# DiamondOutreach.net
KiCad netlist of a schematic drawn in EAGLE
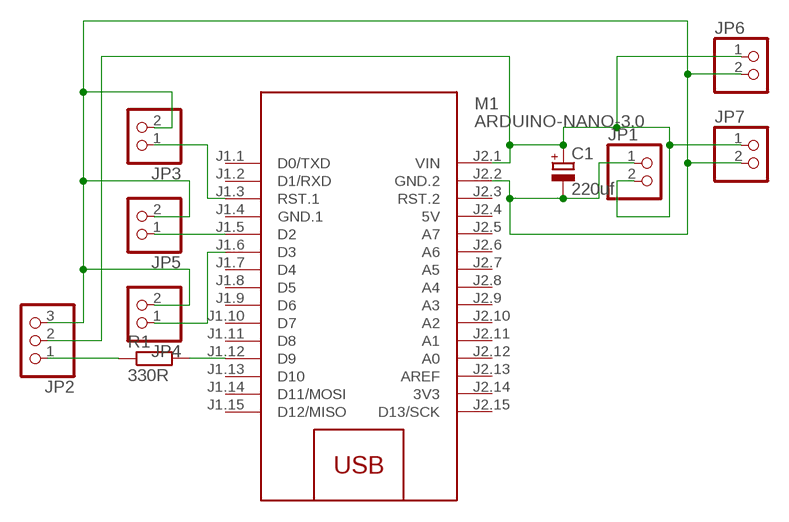
[diagram p0: schematic, sheet 1]

(export (version "E")
  (design (tool "Eeschema 10.0.6"))
  (components
    (comp (ref "C1")
      (value "220uf")
      (footprint "eagle-import:E2,5-6E")
      (libsource (lib "eagle-import") (part "CPOL-EUE2,5-6E"))
    )
    (comp (ref "JP1")
      (value "PINHD-1X2")
      (footprint "eagle-import:1X02")
      (libsource (lib "eagle-import") (part "PINHD-1X2"))
    )
    (comp (ref "JP2")
      (value "PINHD-1X3")
      (footprint "eagle-import:1X03")
      (libsource (lib "eagle-import") (part "PINHD-1X3"))
    )
    (comp (ref "JP3")
      (value "PINHD-1X2")
      (footprint "eagle-import:1X02")
      (libsource (lib "eagle-import") (part "PINHD-1X2"))
    )
    (comp (ref "JP4")
      (value "PINHD-1X2")
      (footprint "eagle-import:1X02")
      (libsource (lib "eagle-import") (part "PINHD-1X2"))
    )
    (comp (ref "JP5")
      (value "PINHD-1X2")
      (footprint "eagle-import:1X02")
      (libsource (lib "eagle-import") (part "PINHD-1X2"))
    )
    (comp (ref "JP6")
      (value "PINHD-1X2")
      (footprint "eagle-import:1X02")
      (libsource (lib "eagle-import") (part "PINHD-1X2"))
    )
    (comp (ref "JP7")
      (value "PINHD-1X2")
      (footprint "eagle-import:1X02")
      (libsource (lib "eagle-import") (part "PINHD-1X2"))
    )
    (comp (ref "M1")
      (value "ARDUINO-NANO-3.0")
      (footprint "eagle-import:ARDUINO-NANO-3.0")
      (libsource (lib "eagle-import") (part "ARDUINO-NANO-3.0"))
    )
    (comp (ref "R1")
      (value "330R")
      (footprint "eagle-import:0204_7")
      (libsource (lib "eagle-import") (part "R-EU_0204/7"))
    )
  )
  (nets
    (net (code "1") (name "/3V3") (class "Default")
      (node (ref "M1") (pin "J2.14") (pinfunction "3V3_J2.14") (pintype "power_in"))
    )
    (net (code "2") (name "/5V") (class "Default")
      (node (ref "M1") (pin "J2.4") (pinfunction "5V_J2.4") (pintype "power_in"))
    )
    (net (code "3") (name "/GND.1") (class "Default")
      (node (ref "M1") (pin "J1.4") (pinfunction "GND.1_J1.4") (pintype "power_in"))
    )
    (net (code "4") (name "Net-(JP2-Pad1)") (class "Default")
      (node (ref "JP2") (pin "1") (pinfunction "1_1") (pintype "passive"))
      (node (ref "R1") (pin "1") (pinfunction "1_1") (pintype "passive"))
    )
    (net (code "5") (name "Net-(M1-D2)") (class "Default")
      (node (ref "JP5") (pin "1") (pinfunction "1_1") (pintype "passive"))
      (node (ref "M1") (pin "J1.5") (pinfunction "D2_J1.5") (pintype "bidirectional"))
    )
    (net (code "6") (name "Net-(M1-D3)") (class "Default")
      (node (ref "JP4") (pin "1") (pinfunction "1_1") (pintype "passive"))
      (node (ref "M1") (pin "J1.6") (pinfunction "D3_J1.6") (pintype "bidirectional"))
    )
    (net (code "7") (name "Net-(M1-D9)") (class "Default")
      (node (ref "M1") (pin "J1.12") (pinfunction "D9_J1.12") (pintype "bidirectional"))
      (node (ref "R1") (pin "2") (pinfunction "2_2") (pintype "passive"))
    )
    (net (code "8") (name "Net-(M1-GND.2)") (class "Default")
      (node (ref "C1") (pin "-") (pinfunction "-_-") (pintype "passive"))
      (node (ref "JP1") (pin "1") (pinfunction "1_1") (pintype "passive"))
      (node (ref "JP2") (pin "3") (pinfunction "3_3") (pintype "passive"))
      (node (ref "JP3") (pin "2") (pinfunction "2_2") (pintype "passive"))
      (node (ref "JP4") (pin "2") (pinfunction "2_2") (pintype "passive"))
      (node (ref "JP5") (pin "2") (pinfunction "2_2") (pintype "passive"))
      (node (ref "JP6") (pin "2") (pinfunction "2_2") (pintype "passive"))
      (node (ref "JP7") (pin "2") (pinfunction "2_2") (pintype "passive"))
      (node (ref "M1") (pin "J2.2") (pinfunction "GND.2_J2.2") (pintype "power_in"))
    )
    (net (code "9") (name "Net-(M1-RST.1)") (class "Default")
      (node (ref "JP3") (pin "1") (pinfunction "1_1") (pintype "passive"))
      (node (ref "M1") (pin "J1.3") (pinfunction "RST.1_J1.3") (pintype "bidirectional"))
    )
    (net (code "10") (name "Net-(M1-VIN)") (class "Default")
      (node (ref "C1") (pin "+") (pinfunction "+_+") (pintype "passive"))
      (node (ref "JP1") (pin "2") (pinfunction "2_2") (pintype "passive"))
      (node (ref "JP2") (pin "2") (pinfunction "2_2") (pintype "passive"))
      (node (ref "JP6") (pin "1") (pinfunction "1_1") (pintype "passive"))
      (node (ref "JP7") (pin "1") (pinfunction "1_1") (pintype "passive"))
      (node (ref "M1") (pin "J2.1") (pinfunction "VIN_J2.1") (pintype "power_in"))
    )
    (net (code "11") (name "unconnected-(M1-A0-PadJ2.12)") (class "Default")
      (node (ref "M1") (pin "J2.12") (pinfunction "A0_J2.12") (pintype "bidirectional"))
    )
    (net (code "12") (name "unconnected-(M1-A1-PadJ2.11)") (class "Default")
      (node (ref "M1") (pin "J2.11") (pinfunction "A1_J2.11") (pintype "bidirectional"))
    )
    (net (code "13") (name "unconnected-(M1-A2-PadJ2.10)") (class "Default")
      (node (ref "M1") (pin "J2.10") (pinfunction "A2_J2.10") (pintype "bidirectional"))
    )
    (net (code "14") (name "unconnected-(M1-A3-PadJ2.9)") (class "Default")
      (node (ref "M1") (pin "J2.9") (pinfunction "A3_J2.9") (pintype "bidirectional"))
    )
    (net (code "15") (name "unconnected-(M1-A4-PadJ2.8)") (class "Default")
      (node (ref "M1") (pin "J2.8") (pinfunction "A4_J2.8") (pintype "bidirectional"))
    )
    (net (code "16") (name "unconnected-(M1-A5-PadJ2.7)") (class "Default")
      (node (ref "M1") (pin "J2.7") (pinfunction "A5_J2.7") (pintype "bidirectional"))
    )
    (net (code "17") (name "unconnected-(M1-A6-PadJ2.6)") (class "Default")
      (node (ref "M1") (pin "J2.6") (pinfunction "A6_J2.6") (pintype "bidirectional"))
    )
    (net (code "18") (name "unconnected-(M1-A7-PadJ2.5)") (class "Default")
      (node (ref "M1") (pin "J2.5") (pinfunction "A7_J2.5") (pintype "bidirectional"))
    )
    (net (code "19") (name "unconnected-(M1-AREF-PadJ2.13)") (class "Default")
      (node (ref "M1") (pin "J2.13") (pinfunction "AREF_J2.13") (pintype "bidirectional"))
    )
    (net (code "20") (name "unconnected-(M1-D0{slash}TXD-PadJ1.1)") (class "Default")
      (node (ref "M1") (pin "J1.1") (pinfunction "D0/TXD_J1.1") (pintype "bidirectional"))
    )
    (net (code "21") (name "unconnected-(M1-D1{slash}RXD-PadJ1.2)") (class "Default")
      (node (ref "M1") (pin "J1.2") (pinfunction "D1/RXD_J1.2") (pintype "bidirectional"))
    )
    (net (code "22") (name "unconnected-(M1-D4-PadJ1.7)") (class "Default")
      (node (ref "M1") (pin "J1.7") (pinfunction "D4_J1.7") (pintype "bidirectional"))
    )
    (net (code "23") (name "unconnected-(M1-D5-PadJ1.8)") (class "Default")
      (node (ref "M1") (pin "J1.8") (pinfunction "D5_J1.8") (pintype "bidirectional"))
    )
    (net (code "24") (name "unconnected-(M1-D6-PadJ1.9)") (class "Default")
      (node (ref "M1") (pin "J1.9") (pinfunction "D6_J1.9") (pintype "bidirectional"))
    )
    (net (code "25") (name "unconnected-(M1-D7-PadJ1.10)") (class "Default")
      (node (ref "M1") (pin "J1.10") (pinfunction "D7_J1.10") (pintype "bidirectional"))
    )
    (net (code "26") (name "unconnected-(M1-D8-PadJ1.11)") (class "Default")
      (node (ref "M1") (pin "J1.11") (pinfunction "D8_J1.11") (pintype "bidirectional"))
    )
    (net (code "27") (name "unconnected-(M1-D10-PadJ1.13)") (class "Default")
      (node (ref "M1") (pin "J1.13") (pinfunction "D10_J1.13") (pintype "bidirectional"))
    )
    (net (code "28") (name "unconnected-(M1-D11{slash}MOSI-PadJ1.14)") (class "Default")
      (node (ref "M1") (pin "J1.14") (pinfunction "D11/MOSI_J1.14") (pintype "bidirectional"))
    )
    (net (code "29") (name "unconnected-(M1-D12{slash}MISO-PadJ1.15)") (class "Default")
      (node (ref "M1") (pin "J1.15") (pinfunction "D12/MISO_J1.15") (pintype "bidirectional"))
    )
    (net (code "30") (name "unconnected-(M1-D13{slash}SCK-PadJ2.15)") (class "Default")
      (node (ref "M1") (pin "J2.15") (pinfunction "D13/SCK_J2.15") (pintype "bidirectional"))
    )
    (net (code "31") (name "unconnected-(M1-RST.2-PadJ2.3)") (class "Default")
      (node (ref "M1") (pin "J2.3") (pinfunction "RST.2_J2.3") (pintype "bidirectional"))
    )
  )
)
